# Smart_Stepper_Fin_-_Kinen_Connector.net
KiCad netlist of a schematic drawn in Altium Designer
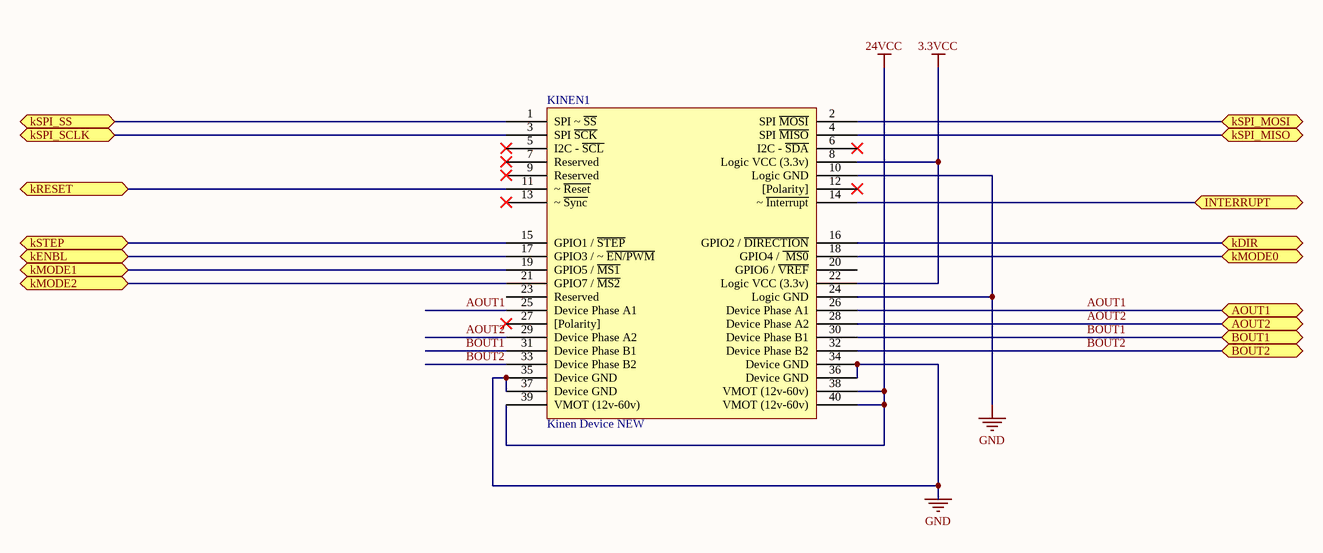
[diagram p0: Smart Stepper Fin - Kinen Connector.SchDoc]

(export (version "E")
  (design (tool "Eeschema 10.0.6"))
  (components
    (comp (ref "KINEN1")
      (value "Kinen Device NEW")
      (footprint "Kinen Port - Device")
      (libsource (lib "ExtruderFinLib") (part "Kinen Device NEW"))
    )
  )
  (nets
    (net (code "1") (name "/AOUT1") (class "Default")
      (node (ref "KINEN1") (pin "25") (pinfunction "Device_Phase_A1_25") (pintype "passive"))
      (node (ref "KINEN1") (pin "26") (pinfunction "Device_Phase_A1_26") (pintype "passive"))
    )
    (net (code "2") (name "/AOUT2") (class "Default")
      (node (ref "KINEN1") (pin "28") (pinfunction "Device_Phase_A2_28") (pintype "passive"))
      (node (ref "KINEN1") (pin "29") (pinfunction "Device_Phase_A2_29") (pintype "passive"))
    )
    (net (code "3") (name "/BOUT1") (class "Default")
      (node (ref "KINEN1") (pin "30") (pinfunction "Device_Phase_B1_30") (pintype "passive"))
      (node (ref "KINEN1") (pin "31") (pinfunction "Device_Phase_B1_31") (pintype "passive"))
    )
    (net (code "4") (name "/BOUT2") (class "Default")
      (node (ref "KINEN1") (pin "32") (pinfunction "Device_Phase_B2_32") (pintype "passive"))
      (node (ref "KINEN1") (pin "33") (pinfunction "Device_Phase_B2_33") (pintype "passive"))
    )
    (net (code "5") (name "/INTERRUPT") (class "Default")
      (node (ref "KINEN1") (pin "14") (pinfunction "~_~{Interrupt}_14") (pintype "passive"))
    )
    (net (code "6") (name "/kDIR") (class "Default")
      (node (ref "KINEN1") (pin "16") (pinfunction "GPIO2_/_~{DIRECTION}_16") (pintype "passive"))
    )
    (net (code "7") (name "/kENBL") (class "Default")
      (node (ref "KINEN1") (pin "17") (pinfunction "GPIO3_/_~_~{EN/PWM}_17") (pintype "passive"))
    )
    (net (code "8") (name "/kMODE0") (class "Default")
      (node (ref "KINEN1") (pin "18") (pinfunction "GPIO4_/_~{_MS0}_18") (pintype "passive"))
    )
    (net (code "9") (name "/kMODE1") (class "Default")
      (node (ref "KINEN1") (pin "19") (pinfunction "GPIO5_/_~{MS1}_19") (pintype "passive"))
    )
    (net (code "10") (name "/kMODE2") (class "Default")
      (node (ref "KINEN1") (pin "21") (pinfunction "GPIO7_/_~{MS2}_21") (pintype "passive"))
    )
    (net (code "11") (name "/kRESET") (class "Default")
      (node (ref "KINEN1") (pin "11") (pinfunction "~_~{Reset}_11") (pintype "passive"))
    )
    (net (code "12") (name "/kSPI_MISO") (class "Default")
      (node (ref "KINEN1") (pin "4") (pinfunction "SPI_~{MISO}_4") (pintype "passive"))
    )
    (net (code "13") (name "/kSPI_MOSI") (class "Default")
      (node (ref "KINEN1") (pin "2") (pinfunction "SPI_~{MOSI}_2") (pintype "passive"))
    )
    (net (code "14") (name "/kSPI_SCLK") (class "Default")
      (node (ref "KINEN1") (pin "3") (pinfunction "SPI_~{SCK}_3") (pintype "passive"))
    )
    (net (code "15") (name "/kSPI_SS") (class "Default")
      (node (ref "KINEN1") (pin "1") (pinfunction "SPI_~_~{SS}_1") (pintype "passive"))
    )
    (net (code "16") (name "/kSTEP") (class "Default")
      (node (ref "KINEN1") (pin "15") (pinfunction "GPIO1_/_~{STEP}_15") (pintype "passive"))
    )
    (net (code "17") (name "3.3VCC") (class "Default")
      (node (ref "KINEN1") (pin "22") (pinfunction "Logic_VCC_(3.3v)_22") (pintype "passive"))
      (node (ref "KINEN1") (pin "8") (pinfunction "Logic_VCC_(3.3v)_8") (pintype "passive"))
    )
    (net (code "18") (name "24VCC") (class "Default")
      (node (ref "KINEN1") (pin "38") (pinfunction "VMOT_(12v-60v)_38") (pintype "passive"))
      (node (ref "KINEN1") (pin "39") (pinfunction "VMOT_(12v-60v)_39") (pintype "passive"))
      (node (ref "KINEN1") (pin "40") (pinfunction "VMOT_(12v-60v)_40") (pintype "passive"))
    )
    (net (code "19") (name "GND") (class "Default")
      (node (ref "KINEN1") (pin "10") (pinfunction "Logic_GND_10") (pintype "passive"))
      (node (ref "KINEN1") (pin "24") (pinfunction "Logic_GND_24") (pintype "passive"))
      (node (ref "KINEN1") (pin "34") (pinfunction "Device_GND_34") (pintype "passive"))
      (node (ref "KINEN1") (pin "35") (pinfunction "Device_GND_35") (pintype "passive"))
      (node (ref "KINEN1") (pin "36") (pinfunction "Device_GND_36") (pintype "passive"))
      (node (ref "KINEN1") (pin "37") (pinfunction "Device_GND_37") (pintype "passive"))
    )
    (net (code "20") (name "unconnected-(KINEN1-GPIO6_{slash}_~{VREF}-Pad20)") (class "Default")
      (node (ref "KINEN1") (pin "20") (pinfunction "GPIO6_/_~{VREF}_20") (pintype "passive"))
    )
    (net (code "21") (name "unconnected-(KINEN1-I2C_-_~{SCL}-Pad5)") (class "Default")
      (node (ref "KINEN1") (pin "5") (pinfunction "I2C_-_~{SCL}_5") (pintype "passive+no_connect"))
    )
    (net (code "22") (name "unconnected-(KINEN1-I2C_-_~{SDA}-Pad6)") (class "Default")
      (node (ref "KINEN1") (pin "6") (pinfunction "I2C_-_~{SDA}_6") (pintype "passive+no_connect"))
    )
    (net (code "23") (name "unconnected-(KINEN1-Reserved-Pad7)") (class "Default")
      (node (ref "KINEN1") (pin "7") (pinfunction "Reserved_7") (pintype "passive+no_connect"))
    )
    (net (code "24") (name "unconnected-(KINEN1-Reserved-Pad9)") (class "Default")
      (node (ref "KINEN1") (pin "9") (pinfunction "Reserved_9") (pintype "passive+no_connect"))
    )
    (net (code "25") (name "unconnected-(KINEN1-Reserved-Pad23)") (class "Default")
      (node (ref "KINEN1") (pin "23") (pinfunction "Reserved_23") (pintype "passive"))
    )
    (net (code "26") (name "unconnected-(KINEN1-[Polarity]-Pad12)") (class "Default")
      (node (ref "KINEN1") (pin "12") (pinfunction "[Polarity]_12") (pintype "passive+no_connect"))
    )
    (net (code "27") (name "unconnected-(KINEN1-[Polarity]-Pad27)") (class "Default")
      (node (ref "KINEN1") (pin "27") (pinfunction "[Polarity]_27") (pintype "passive+no_connect"))
    )
    (net (code "28") (name "unconnected-(KINEN1-~_~{Sync}-Pad13)") (class "Default")
      (node (ref "KINEN1") (pin "13") (pinfunction "~_~{Sync}_13") (pintype "passive+no_connect"))
    )
  )
)
